# Sheet1.net
KiCad netlist of a schematic drawn in Altium Designer
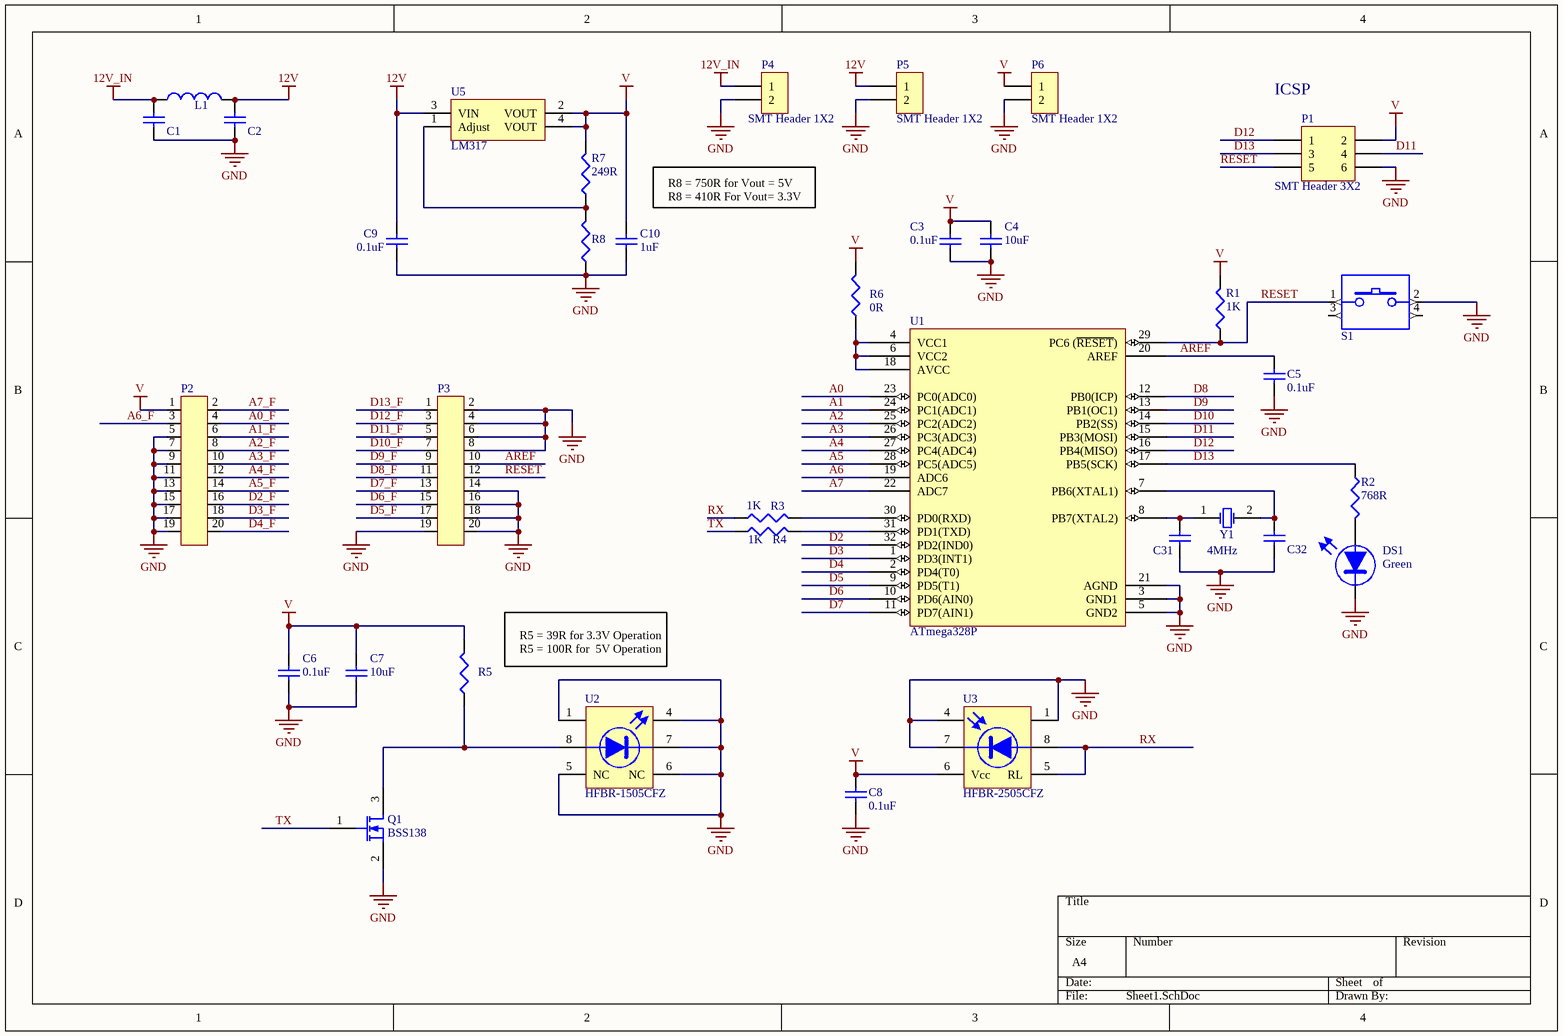
[diagram p0: Sheet1.SchDoc]

(export (version "E")
  (design (tool "Eeschema 10.0.6"))
  (components
    (comp (ref "C1")
      (value "10uF")
      (footprint "CAPC3225X200L")
      (description "10uF, Ceramic Capacitor")
      (fields (field (name "MANUFACTURER") "MURATA") (field (name "PARTNUM") "GRM32DR61E106KA12L"))
      (libsource (lib "Altium_DB") (part "CapStd"))
    )
    (comp (ref "C2")
      (value "10uF")
      (footprint "CAPC3225X200L")
      (description "10uF, Ceramic Capacitor")
      (fields (field (name "MANUFACTURER") "MURATA") (field (name "PARTNUM") "GRM32DR61E106KA12L"))
      (libsource (lib "Altium_DB") (part "CapStd"))
    )
    (comp (ref "C3")
      (value "0.1uF")
      (footprint "CAPC1005X60L")
      (description "0.1uF, Ceramic Capacitor")
      (fields (field (name "MANUFACTURER") "VENKEL") (field (name "PARTNUM") "C0402X7R160-104KN"))
      (libsource (lib "Altium_DB") (part "CapStd"))
    )
    (comp (ref "C4")
      (value "10uF")
      (footprint "CAPC3225X200L")
      (description "10uF, Ceramic Capacitor")
      (fields (field (name "MANUFACTURER") "MURATA") (field (name "PARTNUM") "GRM32DR61E106KA12L"))
      (libsource (lib "Altium_DB") (part "CapStd"))
    )
    (comp (ref "C5")
      (value "0.1uF")
      (footprint "CAPC1005X60L")
      (description "0.1uF, Ceramic Capacitor")
      (fields (field (name "MANUFACTURER") "VENKEL") (field (name "PARTNUM") "C0402X7R160-104KN"))
      (libsource (lib "Altium_DB") (part "CapStd"))
    )
    (comp (ref "C6")
      (value "0.1uF")
      (footprint "CAPC1005X60L")
      (description "0.1uF, Ceramic Capacitor")
      (fields (field (name "MANUFACTURER") "VENKEL") (field (name "PARTNUM") "C0402X7R160-104KN"))
      (libsource (lib "Altium_DB") (part "CapStd"))
    )
    (comp (ref "C7")
      (value "10uF")
      (footprint "CAPC3225X200L")
      (description "10uF, Ceramic Capacitor")
      (fields (field (name "MANUFACTURER") "MURATA") (field (name "PARTNUM") "GRM32DR61E106KA12L"))
      (libsource (lib "Altium_DB") (part "CapStd"))
    )
    (comp (ref "C8")
      (value "0.1uF")
      (footprint "CAPC1005X60L")
      (description "0.1uF, Ceramic Capacitor")
      (fields (field (name "MANUFACTURER") "VENKEL") (field (name "PARTNUM") "C0402X7R160-104KN"))
      (libsource (lib "Altium_DB") (part "CapStd"))
    )
    (comp (ref "C9")
      (value "0.1uF")
      (footprint "CAPC1005X60L")
      (description "0.1uF, Ceramic Capacitor")
      (fields (field (name "MANUFACTURER") "VENKEL") (field (name "PARTNUM") "C0402X7R160-104KN"))
      (libsource (lib "Altium_DB") (part "CapStd"))
    )
    (comp (ref "C10")
      (value "1uF")
      (footprint "CAPC2012X127L")
      (description "1uF, Ceramic Capacitor")
      (fields (field (name "MANUFACTURER") "MURATA") (field (name "PARTNUM") "GRM21BR61C105KA01L"))
      (libsource (lib "Altium_DB") (part "CapStd"))
    )
    (comp (ref "C31")
      (value "1uF")
      (footprint "CAPC2012X127L")
      (description "1uF, Ceramic Capacitor")
      (fields (field (name "MANUFACTURER") "MURATA") (field (name "PARTNUM") "GRM21BR61C105KA01L"))
      (libsource (lib "Altium_DB") (part "CapStd"))
    )
    (comp (ref "C32")
      (value "1uF")
      (footprint "CAPC2012X127L")
      (description "1uF, Ceramic Capacitor")
      (fields (field (name "MANUFACTURER") "MURATA") (field (name "PARTNUM") "GRM21BR61C105KA01L"))
      (libsource (lib "Altium_DB") (part "CapStd"))
    )
    (comp (ref "DS1")
      (value "SML-LX1206GC-TR")
      (footprint "LEDC3216X120N")
      (description "Green, Surface mount, LED, 1206")
      (fields (field (name "MANUFACTURER") "LUMEX") (field (name "COLOUR") "Green"))
      (libsource (lib "Altium_DB") (part "LEDSTD"))
    )
    (comp (ref "L1")
      (value "180R")
      (footprint "INDC1608X130L")
      (description "180 Ohm, Chip Ferrite Brad")
      (fields (field (name "MANUFACTURER") "Murata") (field (name "PARTNUM") "BLM18PG181SN1"))
      (libsource (lib "Altium_DB") (part "IndStd"))
    )
    (comp (ref "P1")
      (value "SMT Header 3X2")
      (footprint "HEADER 3x2, SMT")
      (description "2x3, 2.54 mm Pitch, Male Header, Surface Mount")
      (fields
        (field (name "MANUFACTURER") "AMP")
        (field (name "PARTNUM") "1241050-6")
        (field (name "PUBLISHER") "Altium Limited")
      )
      (libsource (lib "Altium_DB") (part "SMT Header 3X2"))
    )
    (comp (ref "P2")
      (value "N2520-6V0C-RB-WE")
      (footprint "3M_N2520-6V0C-RB-WE")
      (description "2x10, 2.54mm Pitch, Male Shrouded Header")
      (fields (field (name "MANUFACTURER") "3M"))
      (libsource (lib "Altium_DB") (part "con_hdr_2x10_shr"))
    )
    (comp (ref "P3")
      (value "N2520-6V0C-RB-WE")
      (footprint "3M_N2520-6V0C-RB-WE")
      (description "2x10, 2.54mm Pitch, Male Shrouded Header")
      (fields (field (name "MANUFACTURER") "3M"))
      (libsource (lib "Altium_DB") (part "con_hdr_2x10_shr"))
    )
    (comp (ref "P4")
      (value "SMT Header 1X2")
      (footprint "HEADER 1x2, SMT")
      (description "1x2, 2.54 mm Pitch, Male Header, Surface Mount")
      (fields
        (field (name "MANUFACTURER") "AMP")
        (field (name "PARTNUM") "1241050-5")
        (field (name "PUBLISHER") "Altium Limited")
      )
      (libsource (lib "Altium_DB") (part "SMT Header 1X2"))
    )
    (comp (ref "P5")
      (value "SMT Header 1X2")
      (footprint "HEADER 1x2, SMT")
      (description "1x2, 2.54 mm Pitch, Male Header, Surface Mount")
      (fields
        (field (name "MANUFACTURER") "AMP")
        (field (name "PARTNUM") "1241050-5")
        (field (name "PUBLISHER") "Altium Limited")
      )
      (libsource (lib "Altium_DB") (part "SMT Header 1X2"))
    )
    (comp (ref "P6")
      (value "SMT Header 1X2")
      (footprint "HEADER 1x2, SMT")
      (description "1x2, 2.54 mm Pitch, Male Header, Surface Mount")
      (fields
        (field (name "MANUFACTURER") "AMP")
        (field (name "PARTNUM") "1241050-5")
        (field (name "PUBLISHER") "Altium Limited")
      )
      (libsource (lib "Altium_DB") (part "SMT Header 1X2"))
    )
    (comp (ref "Q1")
      (value "BSS138")
      (footprint "SOT95P245X110-3N")
      (description "N-Channel Logic Level Enhancement Mode Field Effect Transistor")
      (fields (field (name "MANUFACTURER") "Fairchild Semiconductor"))
      (libsource (lib "Altium_DB") (part "BSS138"))
    )
    (comp (ref "R1")
      (value "1K")
      (footprint "RESC1005X40L")
      (description "1K, 1.1mm x 0.5mm, Thick Film Resistor")
      (fields (field (name "MANUFACTURER") "ROYALOHM") (field (name "PARTNUM") "0402WGJ0102T1E"))
      (libsource (lib "Altium_DB") (part "ResStd"))
    )
    (comp (ref "R2")
      (value "768R")
      (footprint "RESC1005X40L")
      (description "768R, 1.1mm x 0.5mm, Thick Film Resistor")
      (fields (field (name "MANUFACTURER") "ROYALOHM") (field (name "PARTNUM") "0402WGF7680T1E"))
      (libsource (lib "Altium_DB") (part "ResStd"))
    )
    (comp (ref "R3")
      (value "1K")
      (footprint "RESC1005X40L")
      (description "1K, 1.1mm x 0.5mm, Thick Film Resistor")
      (fields (field (name "MANUFACTURER") "ROYALOHM") (field (name "PARTNUM") "0402WGJ0102T1E"))
      (libsource (lib "Altium_DB") (part "ResStd"))
    )
    (comp (ref "R4")
      (value "1K")
      (footprint "RESC1005X40L")
      (description "1K, 1.1mm x 0.5mm, Thick Film Resistor")
      (fields (field (name "MANUFACTURER") "ROYALOHM") (field (name "PARTNUM") "0402WGJ0102T1E"))
      (libsource (lib "Altium_DB") (part "ResStd"))
    )
    (comp (ref "R5")
      (value "47R")
      (footprint "RESC1005X40L")
      (description "47R, 1.1mm x 0.5mm, Thick Film Resistor")
      (fields (field (name "MANUFACTURER") "ROYALOHM") (field (name "PARTNUM") "0402WGJ0470T1E"))
      (libsource (lib "Altium_DB") (part "ResStd"))
    )
    (comp (ref "R6")
      (value "0R")
      (footprint "RESC1005X40L")
      (description "0R, 1.1mm x 0.5mm, Thick Film Resistor")
      (fields (field (name "MANUFACTURER") "ROYALOHM") (field (name "PARTNUM") "0402WG00000T1E"))
      (libsource (lib "Altium_DB") (part "ResStd"))
    )
    (comp (ref "R7")
      (value "249R")
      (footprint "RESC1005X40L")
      (description "249R, 1.1mm x 0.5mm, Thick Film Resistor")
      (fields (field (name "MANUFACTURER") "ROYALOHM") (field (name "PARTNUM") "0402WGF2490T1E"))
      (libsource (lib "Altium_DB") (part "ResStd"))
    )
    (comp (ref "R8")
      (value "1K")
      (footprint "RESC1005X40L")
      (description "1K, 1.1mm x 0.5mm, Thick Film Resistor")
      (fields (field (name "MANUFACTURER") "ROYALOHM") (field (name "PARTNUM") "0402WGJ0102T1E"))
      (libsource (lib "Altium_DB") (part "ResStd"))
    )
    (comp (ref "S1")
      (value "7914J-1-000-E")
      (footprint "7914J-X-XXX-X")
      (description "4mm, Surface mount, J-Hook, Sealed Key Switch")
      (fields (field (name "MANUFACTURER") "BOURNS"))
      (libsource (lib "Altium_DB") (part "7914X-X-XXX-X"))
    )
    (comp (ref "U1")
      (value "ATmega328P")
      (footprint "TQFP-32A")
      (description "8-Bit Microcontroller with 32KB Flash")
      (fields (field (name "MANUFACTURER") "Atmel") (field (name "PARTNUM") "ATmega328P-AU"))
      (libsource (lib "Altium_DB") (part "ATmega328P"))
    )
    (comp (ref "U2")
      (value "HFBR-1505CFZ")
      (footprint "HFBR-X505XFZ")
      (description "650nm Fibre Optic Transmitter")
      (fields (field (name "MANUFACTURER") "Avago"))
      (libsource (lib "Altium_DB") (part "HFBR-1505CFZ"))
    )
    (comp (ref "U3")
      (value "HFBR-2505CFZ")
      (footprint "HFBR-X505XFZ")
      (description "2MBd Fibre Optic Receiver")
      (fields (field (name "MANUFACTURER") "Avago"))
      (libsource (lib "Altium_DB") (part "HFBR-2505CFZ"))
    )
    (comp (ref "U5")
      (value "LM317")
      (footprint "SOT223_4N")
      (description "Adjustable Voltage regulator 1.25V-37V")
      (fields (field (name "MANUFACTURER") "National Semiconductor") (field (name "PARTNUM") "LM317EMP"))
      (libsource (lib "Altium_DB") (part "LM317"))
    )
    (comp (ref "Y1")
      (value "ATS040B")
      (footprint "HC-49SM")
      (description "4 MHz, Surface mount, Crystal Oscillator")
      (fields (field (name "MANUFACTURER") "CTS") (field (name "FREQUENCY") "4MHz"))
      (libsource (lib "Altium_DB") (part "ATS040B"))
    )
  )
  (nets
    (net (code "1") (name "/A0") (class "Default")
      (node (ref "U1") (pin "23") (pinfunction "PC0(ADC0)_23") (pintype "bidirectional"))
    )
    (net (code "2") (name "/A0_F") (class "Default")
      (node (ref "P2") (pin "4") (pinfunction "4_4") (pintype "passive"))
    )
    (net (code "3") (name "/A1") (class "Default")
      (node (ref "U1") (pin "24") (pinfunction "PC1(ADC1)_24") (pintype "bidirectional"))
    )
    (net (code "4") (name "/A1_F") (class "Default")
      (node (ref "P2") (pin "6") (pinfunction "6_6") (pintype "passive"))
    )
    (net (code "5") (name "/A2") (class "Default")
      (node (ref "U1") (pin "25") (pinfunction "PC2(ADC2)_25") (pintype "bidirectional"))
    )
    (net (code "6") (name "/A2_F") (class "Default")
      (node (ref "P2") (pin "8") (pinfunction "8_8") (pintype "passive"))
    )
    (net (code "7") (name "/A3") (class "Default")
      (node (ref "U1") (pin "26") (pinfunction "PC3(ADC3)_26") (pintype "bidirectional"))
    )
    (net (code "8") (name "/A3_F") (class "Default")
      (node (ref "P2") (pin "10") (pinfunction "10_10") (pintype "passive"))
    )
    (net (code "9") (name "/A4") (class "Default")
      (node (ref "U1") (pin "27") (pinfunction "PC4(ADC4)_27") (pintype "bidirectional"))
    )
    (net (code "10") (name "/A4_F") (class "Default")
      (node (ref "P2") (pin "12") (pinfunction "12_12") (pintype "passive"))
    )
    (net (code "11") (name "/A5") (class "Default")
      (node (ref "U1") (pin "28") (pinfunction "PC5(ADC5)_28") (pintype "bidirectional"))
    )
    (net (code "12") (name "/A5_F") (class "Default")
      (node (ref "P2") (pin "14") (pinfunction "14_14") (pintype "passive"))
    )
    (net (code "13") (name "/A6") (class "Default")
      (node (ref "U1") (pin "19") (pinfunction "ADC6_19") (pintype "passive"))
    )
    (net (code "14") (name "/A6_F") (class "Default")
      (node (ref "P2") (pin "3") (pinfunction "3_3") (pintype "passive"))
    )
    (net (code "15") (name "/A7") (class "Default")
      (node (ref "U1") (pin "22") (pinfunction "ADC7_22") (pintype "passive"))
    )
    (net (code "16") (name "/A7_F") (class "Default")
      (node (ref "P2") (pin "2") (pinfunction "2_2") (pintype "passive"))
    )
    (net (code "17") (name "/AREF") (class "Default")
      (node (ref "C5") (pin "2") (pinfunction "2_2") (pintype "passive"))
      (node (ref "P3") (pin "10") (pinfunction "10_10") (pintype "passive"))
      (node (ref "U1") (pin "20") (pinfunction "AREF_20") (pintype "passive"))
    )
    (net (code "18") (name "/D2") (class "Default")
      (node (ref "U1") (pin "32") (pinfunction "PD2(IND0)_32") (pintype "bidirectional"))
    )
    (net (code "19") (name "/D2_F") (class "Default")
      (node (ref "P2") (pin "16") (pinfunction "16_16") (pintype "passive"))
    )
    (net (code "20") (name "/D3") (class "Default")
      (node (ref "U1") (pin "1") (pinfunction "PD3(INT1)_1") (pintype "bidirectional"))
    )
    (net (code "21") (name "/D3_F") (class "Default")
      (node (ref "P2") (pin "18") (pinfunction "18_18") (pintype "passive"))
    )
    (net (code "22") (name "/D4") (class "Default")
      (node (ref "U1") (pin "2") (pinfunction "PD4(T0)_2") (pintype "bidirectional"))
    )
    (net (code "23") (name "/D4_F") (class "Default")
      (node (ref "P2") (pin "20") (pinfunction "20_20") (pintype "passive"))
    )
    (net (code "24") (name "/D5") (class "Default")
      (node (ref "U1") (pin "9") (pinfunction "PD5(T1)_9") (pintype "bidirectional"))
    )
    (net (code "25") (name "/D5_F") (class "Default")
      (node (ref "P3") (pin "17") (pinfunction "17_17") (pintype "passive"))
    )
    (net (code "26") (name "/D6") (class "Default")
      (node (ref "U1") (pin "10") (pinfunction "PD6(AIN0)_10") (pintype "bidirectional"))
    )
    (net (code "27") (name "/D6_F") (class "Default")
      (node (ref "P3") (pin "15") (pinfunction "15_15") (pintype "passive"))
    )
    (net (code "28") (name "/D7") (class "Default")
      (node (ref "U1") (pin "11") (pinfunction "PD7(AIN1)_11") (pintype "bidirectional"))
    )
    (net (code "29") (name "/D7_F") (class "Default")
      (node (ref "P3") (pin "13") (pinfunction "13_13") (pintype "passive"))
    )
    (net (code "30") (name "/D8") (class "Default")
      (node (ref "U1") (pin "12") (pinfunction "PB0(ICP)_12") (pintype "bidirectional"))
    )
    (net (code "31") (name "/D8_F") (class "Default")
      (node (ref "P3") (pin "11") (pinfunction "11_11") (pintype "passive"))
    )
    (net (code "32") (name "/D9") (class "Default")
      (node (ref "U1") (pin "13") (pinfunction "PB1(OC1)_13") (pintype "bidirectional"))
    )
    (net (code "33") (name "/D9_F") (class "Default")
      (node (ref "P3") (pin "9") (pinfunction "9_9") (pintype "passive"))
    )
    (net (code "34") (name "/D10") (class "Default")
      (node (ref "U1") (pin "14") (pinfunction "PB2(SS)_14") (pintype "bidirectional"))
    )
    (net (code "35") (name "/D10_F") (class "Default")
      (node (ref "P3") (pin "7") (pinfunction "7_7") (pintype "passive"))
    )
    (net (code "36") (name "/D11") (class "Default")
      (node (ref "P1") (pin "4") (pinfunction "4_4") (pintype "passive"))
      (node (ref "U1") (pin "15") (pinfunction "PB3(MOSI)_15") (pintype "bidirectional"))
    )
    (net (code "37") (name "/D11_F") (class "Default")
      (node (ref "P3") (pin "5") (pinfunction "5_5") (pintype "passive"))
    )
    (net (code "38") (name "/D12") (class "Default")
      (node (ref "P1") (pin "1") (pinfunction "1_1") (pintype "passive"))
      (node (ref "U1") (pin "16") (pinfunction "PB4(MISO)_16") (pintype "bidirectional"))
    )
    (net (code "39") (name "/D12_F") (class "Default")
      (node (ref "P3") (pin "3") (pinfunction "3_3") (pintype "passive"))
    )
    (net (code "40") (name "/D13") (class "Default")
      (node (ref "P1") (pin "3") (pinfunction "3_3") (pintype "passive"))
      (node (ref "R2") (pin "1") (pinfunction "1_1") (pintype "passive"))
      (node (ref "U1") (pin "17") (pinfunction "PB5(SCK)_17") (pintype "bidirectional"))
    )
    (net (code "41") (name "/D13_F") (class "Default")
      (node (ref "P3") (pin "1") (pinfunction "1_1") (pintype "passive"))
    )
    (net (code "42") (name "/RESET") (class "Default")
      (node (ref "P1") (pin "5") (pinfunction "5_5") (pintype "passive"))
      (node (ref "P3") (pin "12") (pinfunction "12_12") (pintype "passive"))
      (node (ref "R1") (pin "1") (pinfunction "1_1") (pintype "passive"))
      (node (ref "S1") (pin "1") (pinfunction "1_1") (pintype "output"))
      (node (ref "U1") (pin "29") (pinfunction "PC6_(~{RESET})_29") (pintype "bidirectional"))
    )
    (net (code "43") (name "/RX") (class "Default")
      (node (ref "R3") (pin "1") (pinfunction "1_1") (pintype "passive"))
      (node (ref "U3") (pin "5") (pinfunction "RL_5") (pintype "passive"))
      (node (ref "U3") (pin "8") (pinfunction "Anode_8") (pintype "passive"))
    )
    (net (code "44") (name "/TX") (class "Default")
      (node (ref "Q1") (pin "1") (pinfunction "G_1") (pintype "passive"))
      (node (ref "R4") (pin "1") (pinfunction "1_1") (pintype "passive"))
    )
    (net (code "45") (name "12V") (class "Default")
      (node (ref "C2") (pin "2") (pinfunction "2_2") (pintype "passive"))
      (node (ref "C9") (pin "2") (pinfunction "2_2") (pintype "passive"))
      (node (ref "L1") (pin "2") (pinfunction "2_2") (pintype "passive"))
      (node (ref "P5") (pin "1") (pinfunction "1_1") (pintype "passive"))
      (node (ref "U5") (pin "3") (pinfunction "VIN_3") (pintype "power_in"))
    )
    (net (code "46") (name "12V_IN") (class "Default")
      (node (ref "C1") (pin "2") (pinfunction "2_2") (pintype "passive"))
      (node (ref "L1") (pin "1") (pinfunction "1_1") (pintype "passive"))
      (node (ref "P4") (pin "1") (pinfunction "1_1") (pintype "passive"))
    )
    (net (code "47") (name "GND") (class "Default")
      (node (ref "C1") (pin "1") (pinfunction "1_1") (pintype "passive"))
      (node (ref "C10") (pin "1") (pinfunction "1_1") (pintype "passive"))
      (node (ref "C2") (pin "1") (pinfunction "1_1") (pintype "passive"))
      (node (ref "C3") (pin "1") (pinfunction "1_1") (pintype "passive"))
      (node (ref "C31") (pin "1") (pinfunction "1_1") (pintype "passive"))
      (node (ref "C32") (pin "1") (pinfunction "1_1") (pintype "passive"))
      (node (ref "C4") (pin "1") (pinfunction "1_1") (pintype "passive"))
      (node (ref "C5") (pin "1") (pinfunction "1_1") (pintype "passive"))
      (node (ref "C6") (pin "1") (pinfunction "1_1") (pintype "passive"))
      (node (ref "C7") (pin "1") (pinfunction "1_1") (pintype "passive"))
      (node (ref "C8") (pin "2") (pinfunction "2_2") (pintype "passive"))
      (node (ref "C9") (pin "1") (pinfunction "1_1") (pintype "passive"))
      (node (ref "DS1") (pin "1") (pinfunction "K_1") (pintype "passive"))
      (node (ref "P1") (pin "6") (pinfunction "6_6") (pintype "passive"))
      (node (ref "P2") (pin "11") (pinfunction "11_11") (pintype "passive"))
      (node (ref "P2") (pin "13") (pinfunction "13_13") (pintype "passive"))
      (node (ref "P2") (pin "15") (pinfunction "15_15") (pintype "passive"))
      (node (ref "P2") (pin "17") (pinfunction "17_17") (pintype "passive"))
      (node (ref "P2") (pin "19") (pinfunction "19_19") (pintype "passive"))
      (node (ref "P2") (pin "5") (pinfunction "5_5") (pintype "passive"))
      (node (ref "P2") (pin "7") (pinfunction "7_7") (pintype "passive"))
      (node (ref "P2") (pin "9") (pinfunction "9_9") (pintype "passive"))
      (node (ref "P3") (pin "14") (pinfunction "14_14") (pintype "passive"))
      (node (ref "P3") (pin "16") (pinfunction "16_16") (pintype "passive"))
      (node (ref "P3") (pin "18") (pinfunction "18_18") (pintype "passive"))
      (node (ref "P3") (pin "19") (pinfunction "19_19") (pintype "passive"))
      (node (ref "P3") (pin "2") (pinfunction "2_2") (pintype "passive"))
      (node (ref "P3") (pin "20") (pinfunction "20_20") (pintype "passive"))
      (node (ref "P3") (pin "4") (pinfunction "4_4") (pintype "passive"))
      (node (ref "P3") (pin "6") (pinfunction "6_6") (pintype "passive"))
      (node (ref "P3") (pin "8") (pinfunction "8_8") (pintype "passive"))
      (node (ref "P4") (pin "2") (pinfunction "2_2") (pintype "passive"))
      (node (ref "P5") (pin "2") (pinfunction "2_2") (pintype "passive"))
      (node (ref "P6") (pin "2") (pinfunction "2_2") (pintype "passive"))
      (node (ref "Q1") (pin "2") (pinfunction "S_2") (pintype "passive"))
      (node (ref "R8") (pin "1") (pinfunction "1_1") (pintype "passive"))
      (node (ref "S1") (pin "2") (pinfunction "2_2") (pintype "output"))
      (node (ref "U1") (pin "21") (pinfunction "AGND_21") (pintype "passive"))
      (node (ref "U1") (pin "3") (pinfunction "GND1_3") (pintype "power_in"))
      (node (ref "U1") (pin "5") (pinfunction "GND2_5") (pintype "power_in"))
      (node (ref "U2") (pin "1") (pintype "passive"))
      (node (ref "U2") (pin "4") (pintype "passive"))
      (node (ref "U2") (pin "5") (pinfunction "NC_5") (pintype "passive"))
      (node (ref "U2") (pin "6") (pinfunction "NC_6") (pintype "passive"))
      (node (ref "U2") (pin "7") (pinfunction "Cathode_7") (pintype "passive"))
      (node (ref "U3") (pin "1") (pintype "passive"))
      (node (ref "U3") (pin "4") (pintype "passive"))
      (node (ref "U3") (pin "7") (pinfunction "Cathode_7") (pintype "passive"))
    )
    (net (code "48") (name "Net-(DS1-A)") (class "Default")
      (node (ref "DS1") (pin "2") (pinfunction "A_2") (pintype "passive"))
      (node (ref "R2") (pin "2") (pinfunction "2_2") (pintype "passive"))
    )
    (net (code "49") (name "Net-(Q1-D)") (class "Default")
      (node (ref "Q1") (pin "3") (pinfunction "D_3") (pintype "passive"))
      (node (ref "R5") (pin "1") (pinfunction "1_1") (pintype "passive"))
      (node (ref "U2") (pin "8") (pinfunction "Anode_8") (pintype "passive"))
    )
    (net (code "50") (name "Net-(U1-AVCC)") (class "Default")
      (node (ref "R6") (pin "1") (pinfunction "1_1") (pintype "passive"))
      (node (ref "U1") (pin "18") (pinfunction "AVCC_18") (pintype "power_in"))
      (node (ref "U1") (pin "4") (pinfunction "VCC1_4") (pintype "power_in"))
      (node (ref "U1") (pin "6") (pinfunction "VCC2_6") (pintype "power_in"))
    )
    (net (code "51") (name "Net-(U1-PB6(XTAL1))") (class "Default")
      (node (ref "C32") (pin "2") (pinfunction "2_2") (pintype "passive"))
      (node (ref "U1") (pin "7") (pinfunction "PB6(XTAL1)_7") (pintype "bidirectional"))
      (node (ref "Y1") (pin "2") (pinfunction "2_2") (pintype "passive"))
    )
    (net (code "52") (name "Net-(U1-PB7(XTAL2))") (class "Default")
      (node (ref "C31") (pin "2") (pinfunction "2_2") (pintype "passive"))
      (node (ref "U1") (pin "8") (pinfunction "PB7(XTAL2)_8") (pintype "bidirectional"))
      (node (ref "Y1") (pin "1") (pinfunction "1_1") (pintype "passive"))
    )
    (net (code "53") (name "Net-(U1-PD0(RXD))") (class "Default")
      (node (ref "R3") (pin "2") (pinfunction "2_2") (pintype "passive"))
      (node (ref "U1") (pin "30") (pinfunction "PD0(RXD)_30") (pintype "bidirectional"))
    )
    (net (code "54") (name "Net-(U1-PD1(TXD))") (class "Default")
      (node (ref "R4") (pin "2") (pinfunction "2_2") (pintype "passive"))
      (node (ref "U1") (pin "31") (pinfunction "PD1(TXD)_31") (pintype "bidirectional"))
    )
    (net (code "55") (name "Net-(U5-Adjust)") (class "Default")
      (node (ref "R7") (pin "1") (pinfunction "1_1") (pintype "passive"))
      (node (ref "R8") (pin "2") (pinfunction "2_2") (pintype "passive"))
      (node (ref "U5") (pin "1") (pinfunction "Adjust_1") (pintype "passive"))
    )
    (net (code "56") (name "V") (class "Default")
      (node (ref "C10") (pin "2") (pinfunction "2_2") (pintype "passive"))
      (node (ref "C3") (pin "2") (pinfunction "2_2") (pintype "passive"))
      (node (ref "C4") (pin "2") (pinfunction "2_2") (pintype "passive"))
      (node (ref "C6") (pin "2") (pinfunction "2_2") (pintype "passive"))
      (node (ref "C7") (pin "2") (pinfunction "2_2") (pintype "passive"))
      (node (ref "C8") (pin "1") (pinfunction "1_1") (pintype "passive"))
      (node (ref "P1") (pin "2") (pinfunction "2_2") (pintype "passive"))
      (node (ref "P2") (pin "1") (pinfunction "1_1") (pintype "passive"))
      (node (ref "P6") (pin "1") (pinfunction "1_1") (pintype "passive"))
      (node (ref "R1") (pin "2") (pinfunction "2_2") (pintype "passive"))
      (node (ref "R5") (pin "2") (pinfunction "2_2") (pintype "passive"))
      (node (ref "R6") (pin "2") (pinfunction "2_2") (pintype "passive"))
      (node (ref "R7") (pin "2") (pinfunction "2_2") (pintype "passive"))
      (node (ref "U3") (pin "6") (pinfunction "Vcc_6") (pintype "power_in"))
      (node (ref "U5") (pin "2") (pinfunction "VOUT_2") (pintype "power_in"))
      (node (ref "U5") (pin "4") (pinfunction "VOUT_4") (pintype "power_in"))
    )
    (net (code "57") (name "unconnected-(S1-Pad3)") (class "Default")
      (node (ref "S1") (pin "3") (pinfunction "3_3") (pintype "output"))
    )
    (net (code "58") (name "unconnected-(S1-Pad4)") (class "Default")
      (node (ref "S1") (pin "4") (pinfunction "4_4") (pintype "output"))
    )
  )
)
